# 1-BitSelect.net
KiCad netlist of a schematic drawn in EAGLE
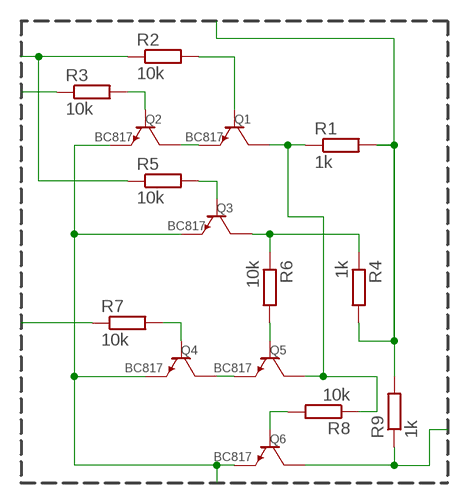
[diagram p0: schematic, sheet 1]

(export (version "E")
  (design (tool "Eeschema 10.0.6"))
  (components
    (comp (ref "Q1")
      (value "BC817")
      (footprint "eagle-import:SOT23")
      (libsource (lib "eagle-import") (part "TRANSISTOR-NPN-GENERIC-SOT23-BECDEFAULT"))
    )
    (comp (ref "Q2")
      (value "BC817")
      (footprint "eagle-import:SOT23")
      (libsource (lib "eagle-import") (part "TRANSISTOR-NPN-GENERIC-SOT23-BECDEFAULT"))
    )
    (comp (ref "Q3")
      (value "BC817")
      (footprint "eagle-import:SOT23")
      (libsource (lib "eagle-import") (part "TRANSISTOR-NPN-GENERIC-SOT23-BECDEFAULT"))
    )
    (comp (ref "Q4")
      (value "BC817")
      (footprint "eagle-import:SOT23")
      (libsource (lib "eagle-import") (part "TRANSISTOR-NPN-GENERIC-SOT23-BECDEFAULT"))
    )
    (comp (ref "Q5")
      (value "BC817")
      (footprint "eagle-import:SOT23")
      (libsource (lib "eagle-import") (part "TRANSISTOR-NPN-GENERIC-SOT23-BECDEFAULT"))
    )
    (comp (ref "Q6")
      (value "BC817")
      (footprint "eagle-import:SOT23")
      (libsource (lib "eagle-import") (part "TRANSISTOR-NPN-GENERIC-SOT23-BECDEFAULT"))
    )
    (comp (ref "R1")
      (value "1k")
      (footprint "eagle-import:R0603")
      (libsource (lib "eagle-import") (part "R-EU_R0603"))
    )
    (comp (ref "R2")
      (value "10k")
      (footprint "eagle-import:R0603")
      (libsource (lib "eagle-import") (part "R-EU_R0603"))
    )
    (comp (ref "R3")
      (value "10k")
      (footprint "eagle-import:R0603")
      (libsource (lib "eagle-import") (part "R-EU_R0603"))
    )
    (comp (ref "R4")
      (value "1k")
      (footprint "eagle-import:R0603")
      (libsource (lib "eagle-import") (part "R-EU_R0603"))
    )
    (comp (ref "R5")
      (value "10k")
      (footprint "eagle-import:R0603")
      (libsource (lib "eagle-import") (part "R-EU_R0603"))
    )
    (comp (ref "R6")
      (value "10k")
      (footprint "eagle-import:R0603")
      (libsource (lib "eagle-import") (part "R-EU_R0603"))
    )
    (comp (ref "R7")
      (value "10k")
      (footprint "eagle-import:R0603")
      (libsource (lib "eagle-import") (part "R-EU_R0603"))
    )
    (comp (ref "R8")
      (value "10k")
      (footprint "eagle-import:R0603")
      (libsource (lib "eagle-import") (part "R-EU_R0603"))
    )
    (comp (ref "R9")
      (value "1k")
      (footprint "eagle-import:R0603")
      (libsource (lib "eagle-import") (part "R-EU_R0603"))
    )
  )
  (nets
    (net (code "1") (name "Net-(Q1-BASE)") (class "Default")
      (node (ref "Q1") (pin "P$1") (pinfunction "BASE_P$1") (pintype "bidirectional"))
      (node (ref "R2") (pin "2") (pinfunction "2_2") (pintype "passive"))
    )
    (net (code "2") (name "Net-(Q1-COLLECTOR)") (class "Default")
      (node (ref "Q1") (pin "P$3") (pinfunction "COLLECTOR_P$3") (pintype "bidirectional"))
      (node (ref "Q5") (pin "P$3") (pinfunction "COLLECTOR_P$3") (pintype "bidirectional"))
      (node (ref "R1") (pin "1") (pinfunction "1_1") (pintype "passive"))
      (node (ref "R8") (pin "1") (pinfunction "1_1") (pintype "passive"))
    )
    (net (code "3") (name "Net-(Q1-EMITTER)") (class "Default")
      (node (ref "Q1") (pin "P$2") (pinfunction "EMITTER_P$2") (pintype "bidirectional"))
      (node (ref "Q2") (pin "P$3") (pinfunction "COLLECTOR_P$3") (pintype "bidirectional"))
    )
    (net (code "4") (name "Net-(Q2-BASE)") (class "Default")
      (node (ref "Q2") (pin "P$1") (pinfunction "BASE_P$1") (pintype "bidirectional"))
      (node (ref "R3") (pin "2") (pinfunction "2_2") (pintype "passive"))
    )
    (net (code "5") (name "Net-(Q2-EMITTER)") (class "Default")
      (node (ref "Q2") (pin "P$2") (pinfunction "EMITTER_P$2") (pintype "bidirectional"))
      (node (ref "Q3") (pin "P$2") (pinfunction "EMITTER_P$2") (pintype "bidirectional"))
      (node (ref "Q4") (pin "P$2") (pinfunction "EMITTER_P$2") (pintype "bidirectional"))
      (node (ref "Q6") (pin "P$2") (pinfunction "EMITTER_P$2") (pintype "bidirectional"))
    )
    (net (code "6") (name "Net-(Q3-BASE)") (class "Default")
      (node (ref "Q3") (pin "P$1") (pinfunction "BASE_P$1") (pintype "bidirectional"))
      (node (ref "R5") (pin "2") (pinfunction "2_2") (pintype "passive"))
    )
    (net (code "7") (name "Net-(Q3-COLLECTOR)") (class "Default")
      (node (ref "Q3") (pin "P$3") (pinfunction "COLLECTOR_P$3") (pintype "bidirectional"))
      (node (ref "R4") (pin "1") (pinfunction "1_1") (pintype "passive"))
      (node (ref "R6") (pin "1") (pinfunction "1_1") (pintype "passive"))
    )
    (net (code "8") (name "Net-(Q4-BASE)") (class "Default")
      (node (ref "Q4") (pin "P$1") (pinfunction "BASE_P$1") (pintype "bidirectional"))
      (node (ref "R7") (pin "2") (pinfunction "2_2") (pintype "passive"))
    )
    (net (code "9") (name "Net-(Q4-COLLECTOR)") (class "Default")
      (node (ref "Q4") (pin "P$3") (pinfunction "COLLECTOR_P$3") (pintype "bidirectional"))
      (node (ref "Q5") (pin "P$2") (pinfunction "EMITTER_P$2") (pintype "bidirectional"))
    )
    (net (code "10") (name "Net-(Q5-BASE)") (class "Default")
      (node (ref "Q5") (pin "P$1") (pinfunction "BASE_P$1") (pintype "bidirectional"))
      (node (ref "R6") (pin "2") (pinfunction "2_2") (pintype "passive"))
    )
    (net (code "11") (name "Net-(Q6-BASE)") (class "Default")
      (node (ref "Q6") (pin "P$1") (pinfunction "BASE_P$1") (pintype "bidirectional"))
      (node (ref "R8") (pin "2") (pinfunction "2_2") (pintype "passive"))
    )
    (net (code "12") (name "Net-(Q6-COLLECTOR)") (class "Default")
      (node (ref "Q6") (pin "P$3") (pinfunction "COLLECTOR_P$3") (pintype "bidirectional"))
      (node (ref "R9") (pin "1") (pinfunction "1_1") (pintype "passive"))
    )
    (net (code "13") (name "Net-(R1-Pad2)") (class "Default")
      (node (ref "R1") (pin "2") (pinfunction "2_2") (pintype "passive"))
      (node (ref "R4") (pin "2") (pinfunction "2_2") (pintype "passive"))
      (node (ref "R9") (pin "2") (pinfunction "2_2") (pintype "passive"))
    )
    (net (code "14") (name "Net-(R2-Pad1)") (class "Default")
      (node (ref "R2") (pin "1") (pinfunction "1_1") (pintype "passive"))
      (node (ref "R5") (pin "1") (pinfunction "1_1") (pintype "passive"))
    )
    (net (code "15") (name "unconnected-(R3-Pad1)") (class "Default")
      (node (ref "R3") (pin "1") (pinfunction "1_1") (pintype "passive"))
    )
    (net (code "16") (name "unconnected-(R7-Pad1)") (class "Default")
      (node (ref "R7") (pin "1") (pinfunction "1_1") (pintype "passive"))
    )
  )
)
